# VentaConnected_ESP8266_V0_01_2017-11-26.net
KiCad netlist of a schematic drawn in EAGLE
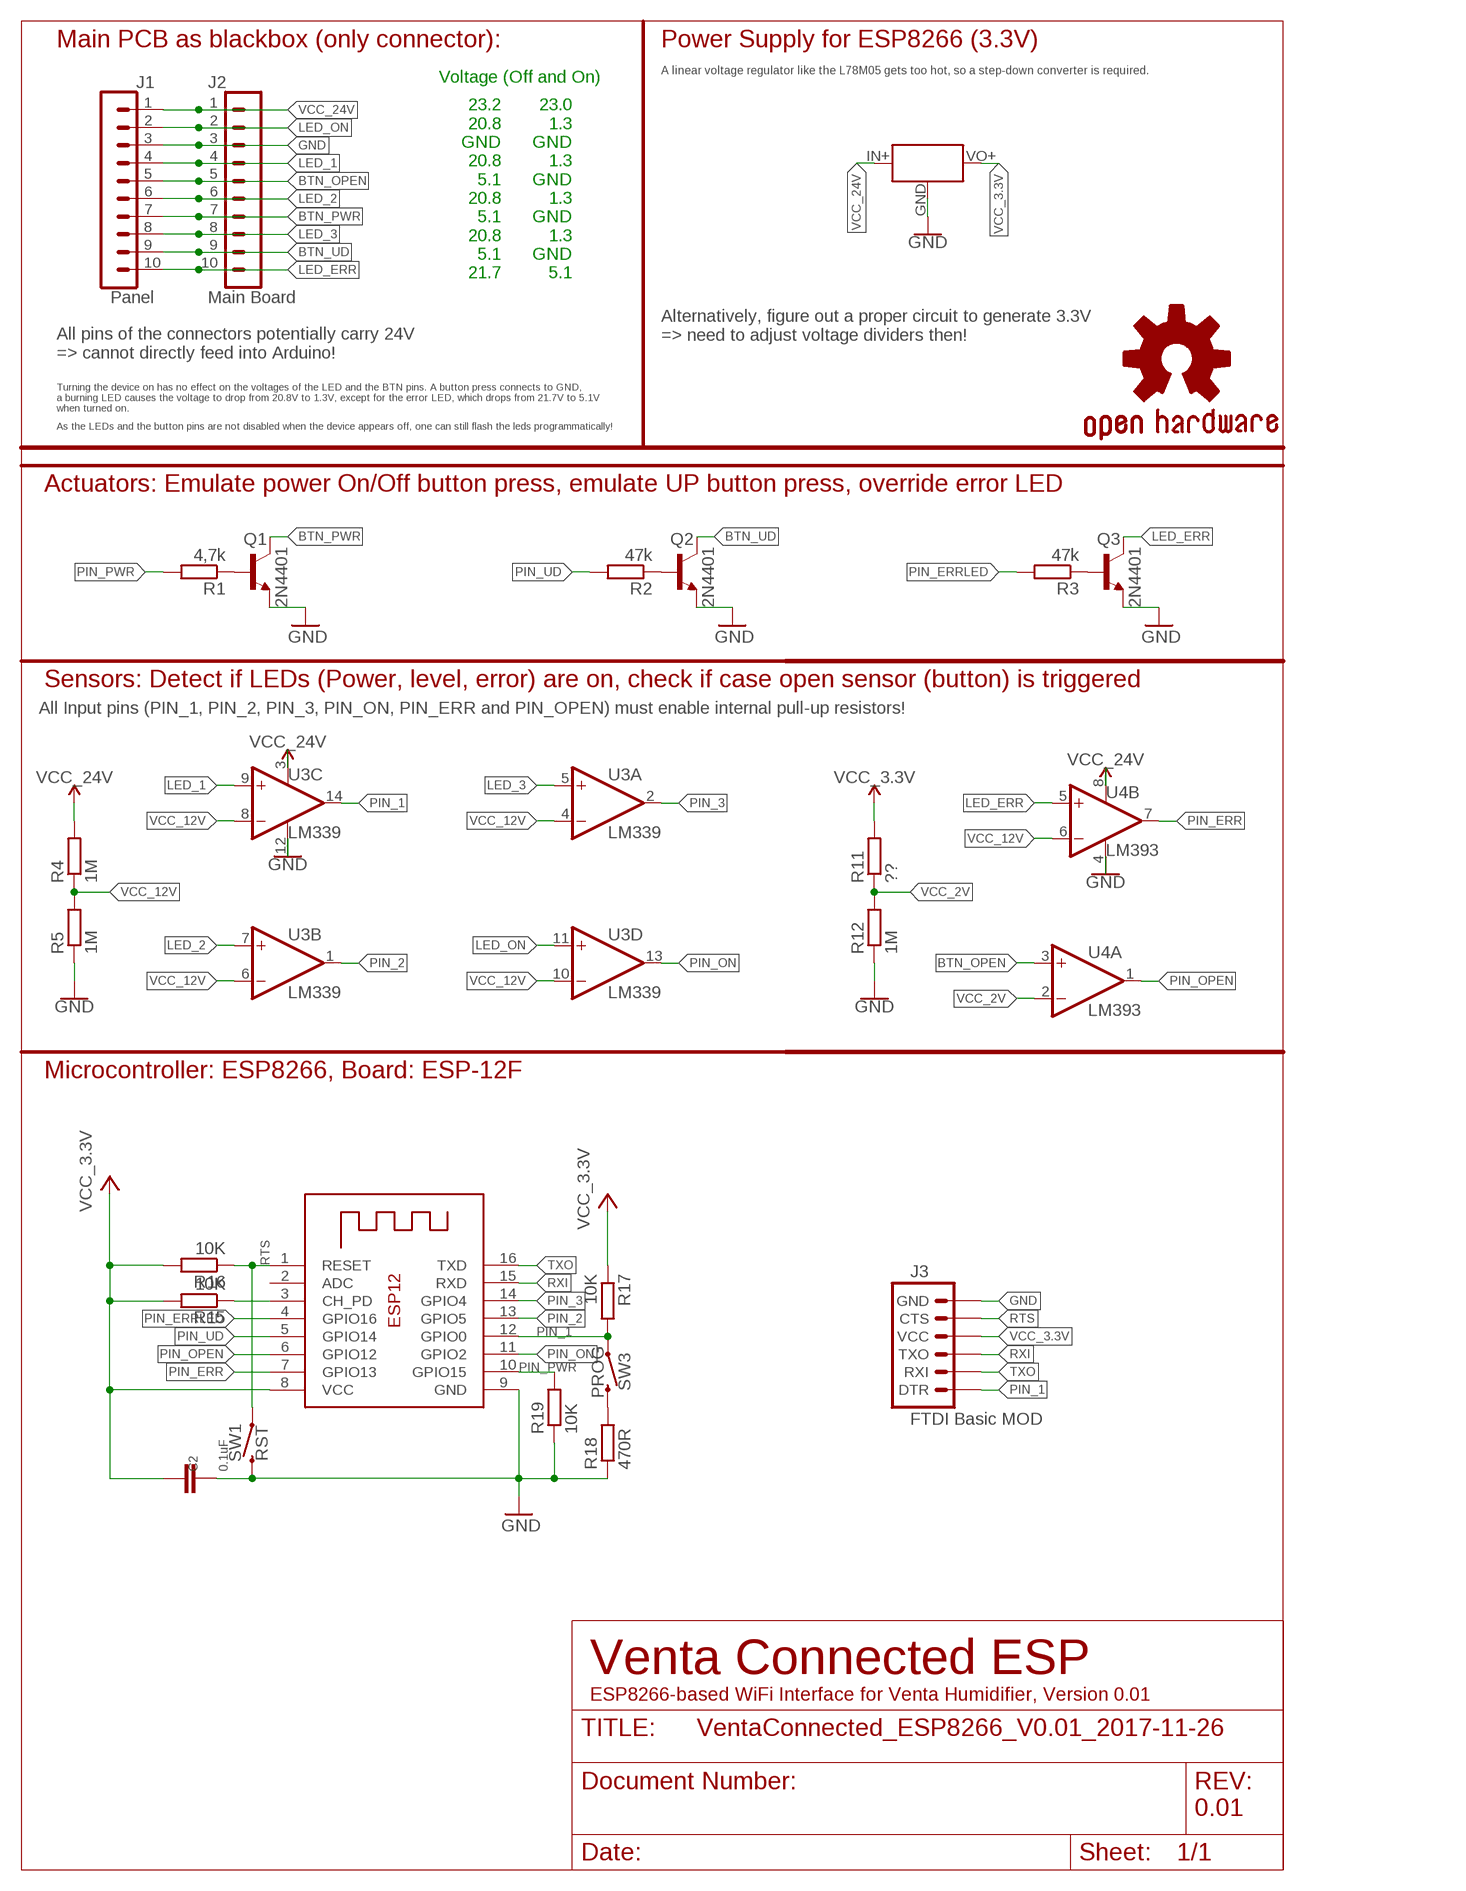
[diagram p0: schematic, sheet 1]

(export (version "E")
  (design (tool "Eeschema 10.0.6"))
  (components
    (comp (ref "C2")
      (value "0.1uF")
      (footprint "eagle-import:C0805")
      (libsource (lib "eagle-import") (part "C-EUC0805"))
    )
    (comp (ref "GOLD_ORB_SM1")
      (value "OSHWLOGO_GOLD_ORB_SM")
      (footprint "eagle-import:OSHW2")
      (libsource (lib "eagle-import") (part "OSHWLOGO_GOLD_ORB_SM"))
    )
    (comp (ref "J1")
      (value "Panel")
      (footprint "eagle-import:2X5-SHROUDED")
      (libsource (lib "eagle-import") (part "CONN_05X2SHD"))
    )
    (comp (ref "J2")
      (value "Main Board")
      (footprint "eagle-import:2X5")
      (libsource (lib "eagle-import") (part "CONN_05X2PTH"))
    )
    (comp (ref "J3")
      (value "FTDI Basic MOD")
      (footprint "eagle-import:1X06")
      (libsource (lib "eagle-import") (part "ARDUINO_SERIAL_PROGRAMPTH"))
    )
    (comp (ref "Q1")
      (value "2N4401")
      (footprint "eagle-import:SOT23-BEC")
      (libsource (lib "eagle-import") (part "-NPN-SOT23-BECMMBT4401LT1"))
    )
    (comp (ref "Q2")
      (value "2N4401")
      (footprint "eagle-import:SOT23-BEC")
      (libsource (lib "eagle-import") (part "-NPN-SOT23-BECMMBT4401LT1"))
    )
    (comp (ref "Q3")
      (value "2N4401")
      (footprint "eagle-import:SOT23-BEC")
      (libsource (lib "eagle-import") (part "-NPN-SOT23-BECMMBT4401LT1"))
    )
    (comp (ref "R1")
      (value "4,7k")
      (footprint "eagle-import:R0805")
      (libsource (lib "eagle-import") (part "resistor_348_R-EU_R0805"))
    )
    (comp (ref "R2")
      (value "47k")
      (footprint "eagle-import:R0805")
      (libsource (lib "eagle-import") (part "resistor_348_R-EU_R0805"))
    )
    (comp (ref "R3")
      (value "47k")
      (footprint "eagle-import:R0805")
      (libsource (lib "eagle-import") (part "resistor_348_R-EU_R0805"))
    )
    (comp (ref "R4")
      (value "1M")
      (footprint "eagle-import:R0805")
      (libsource (lib "eagle-import") (part "resistor_348_R-EU_R0805"))
    )
    (comp (ref "R5")
      (value "1M")
      (footprint "eagle-import:R0805")
      (libsource (lib "eagle-import") (part "resistor_348_R-EU_R0805"))
    )
    (comp (ref "R11")
      (value "??")
      (footprint "eagle-import:R0805")
      (libsource (lib "eagle-import") (part "resistor_348_R-EU_R0805"))
    )
    (comp (ref "R12")
      (value "1M")
      (footprint "eagle-import:R0805")
      (libsource (lib "eagle-import") (part "resistor_348_R-EU_R0805"))
    )
    (comp (ref "R15")
      (value "10K")
      (footprint "eagle-import:R0805")
      (libsource (lib "eagle-import") (part "R-EU_R0805"))
    )
    (comp (ref "R16")
      (value "10K")
      (footprint "eagle-import:R0805")
      (libsource (lib "eagle-import") (part "R-EU_R0805"))
    )
    (comp (ref "R17")
      (value "10K")
      (footprint "eagle-import:R0805")
      (libsource (lib "eagle-import") (part "R-EU_R0805"))
    )
    (comp (ref "R18")
      (value "470R")
      (footprint "eagle-import:R0805")
      (libsource (lib "eagle-import") (part "R-EU_R0805"))
    )
    (comp (ref "R19")
      (value "10K")
      (footprint "eagle-import:R0805")
      (libsource (lib "eagle-import") (part "R-EU_R0805"))
    )
    (comp (ref "SW1")
      (value "RST")
      (footprint "eagle-import:TACTILE_SWITCH_SMD_6.0X3.5MM")
      (libsource (lib "eagle-import") (part "MOMENTARY-SWITCH-SPST-SMD-6.0X3.5MM"))
    )
    (comp (ref "SW3")
      (value "PROG")
      (footprint "eagle-import:TACTILE_SWITCH_SMD_6.0X3.5MM")
      (libsource (lib "eagle-import") (part "MOMENTARY-SWITCH-SPST-SMD-6.0X3.5MM"))
    )
    (comp (ref "U2")
      (value "3.3V_BUCK_CONVERTER")
      (footprint "eagle-import:MINI_BUCK_CONVERTER_UPDOWN")
      (libsource (lib "eagle-import") (part "MINI_BUCK_CONVERTER_UPSIDEDOWN"))
    )
    (comp (ref "U3")
      (value "LM339")
      (footprint "eagle-import:SO14")
      (libsource (lib "eagle-import") (part "TLC339D"))
    )
    (comp (ref "U4")
      (value "LM393")
      (footprint "eagle-import:SO08")
      (libsource (lib "eagle-import") (part "LM393D"))
    )
    (comp (ref "X2")
      (value "ESP-12e")
      (footprint "eagle-import:ESP-12")
      (libsource (lib "eagle-import") (part "ESP-12"))
    )
  )
  (nets
    (net (code "1") (name "BTN_OPEN") (class "Default")
      (node (ref "J1") (pin "5") (pinfunction "5_5") (pintype "passive"))
      (node (ref "J2") (pin "5") (pinfunction "5_5") (pintype "passive"))
      (node (ref "U4") (pin "3") (pinfunction "+IN_3") (pintype "input"))
    )
    (net (code "2") (name "BTN_PWR") (class "Default")
      (node (ref "J1") (pin "7") (pinfunction "7_7") (pintype "passive"))
      (node (ref "J2") (pin "7") (pinfunction "7_7") (pintype "passive"))
      (node (ref "Q1") (pin "C") (pinfunction "C_C") (pintype "passive"))
    )
    (net (code "3") (name "BTN_UD") (class "Default")
      (node (ref "J1") (pin "9") (pinfunction "9_9") (pintype "passive"))
      (node (ref "J2") (pin "9") (pinfunction "9_9") (pintype "passive"))
      (node (ref "Q2") (pin "C") (pinfunction "C_C") (pintype "passive"))
    )
    (net (code "4") (name "GND") (class "Default")
      (node (ref "C2") (pin "1") (pinfunction "1_1") (pintype "passive"))
      (node (ref "J1") (pin "3") (pinfunction "3_3") (pintype "passive"))
      (node (ref "J2") (pin "3") (pinfunction "3_3") (pintype "passive"))
      (node (ref "J3") (pin "6") (pinfunction "GND_6") (pintype "passive"))
      (node (ref "Q1") (pin "E") (pinfunction "E_E") (pintype "passive"))
      (node (ref "Q2") (pin "E") (pinfunction "E_E") (pintype "passive"))
      (node (ref "Q3") (pin "E") (pinfunction "E_E") (pintype "passive"))
      (node (ref "R12") (pin "1") (pinfunction "1_1") (pintype "passive"))
      (node (ref "R18") (pin "1") (pinfunction "1_1") (pintype "passive"))
      (node (ref "R19") (pin "1") (pinfunction "1_1") (pintype "passive"))
      (node (ref "R5") (pin "1") (pinfunction "1_1") (pintype "passive"))
      (node (ref "SW1") (pin "2") (pinfunction "2_2") (pintype "passive"))
      (node (ref "U2") (pin "GND") (pinfunction "GND_GND") (pintype "bidirectional"))
      (node (ref "U3") (pin "12") (pinfunction "V-_12") (pintype "power_in"))
      (node (ref "U4") (pin "4") (pinfunction "V-_4") (pintype "power_in"))
      (node (ref "X2") (pin "9") (pinfunction "GND_9") (pintype "power_in"))
    )
    (net (code "5") (name "LED_1") (class "Default")
      (node (ref "J1") (pin "4") (pinfunction "4_4") (pintype "passive"))
      (node (ref "J2") (pin "4") (pinfunction "4_4") (pintype "passive"))
      (node (ref "U3") (pin "9") (pinfunction "+IN_9") (pintype "input"))
    )
    (net (code "6") (name "LED_2") (class "Default")
      (node (ref "J1") (pin "6") (pinfunction "6_6") (pintype "passive"))
      (node (ref "J2") (pin "6") (pinfunction "6_6") (pintype "passive"))
      (node (ref "U3") (pin "7") (pinfunction "+IN_7") (pintype "input"))
    )
    (net (code "7") (name "LED_3") (class "Default")
      (node (ref "J1") (pin "8") (pinfunction "8_8") (pintype "passive"))
      (node (ref "J2") (pin "8") (pinfunction "8_8") (pintype "passive"))
      (node (ref "U3") (pin "5") (pinfunction "+IN_5") (pintype "input"))
    )
    (net (code "8") (name "LED_ERR") (class "Default")
      (node (ref "J1") (pin "10") (pinfunction "10_10") (pintype "passive"))
      (node (ref "J2") (pin "10") (pinfunction "10_10") (pintype "passive"))
      (node (ref "Q3") (pin "C") (pinfunction "C_C") (pintype "passive"))
      (node (ref "U4") (pin "5") (pinfunction "+IN_5") (pintype "input"))
    )
    (net (code "9") (name "LED_ON") (class "Default")
      (node (ref "J1") (pin "2") (pinfunction "2_2") (pintype "passive"))
      (node (ref "J2") (pin "2") (pinfunction "2_2") (pintype "passive"))
      (node (ref "U3") (pin "11") (pinfunction "+IN_11") (pintype "input"))
    )
    (net (code "10") (name "Net-(Q1-PadB)") (class "Default")
      (node (ref "Q1") (pin "B") (pinfunction "B_B") (pintype "passive"))
      (node (ref "R1") (pin "1") (pinfunction "1_1") (pintype "passive"))
    )
    (net (code "11") (name "Net-(Q2-PadB)") (class "Default")
      (node (ref "Q2") (pin "B") (pinfunction "B_B") (pintype "passive"))
      (node (ref "R2") (pin "1") (pinfunction "1_1") (pintype "passive"))
    )
    (net (code "12") (name "Net-(Q3-PadB)") (class "Default")
      (node (ref "Q3") (pin "B") (pinfunction "B_B") (pintype "passive"))
      (node (ref "R3") (pin "1") (pinfunction "1_1") (pintype "passive"))
    )
    (net (code "13") (name "Net-(R18-Pad2)") (class "Default")
      (node (ref "R18") (pin "2") (pinfunction "2_2") (pintype "passive"))
      (node (ref "SW3") (pin "2") (pinfunction "2_2") (pintype "passive"))
    )
    (net (code "14") (name "Net-(X2-CH_PD)") (class "Default")
      (node (ref "R15") (pin "1") (pinfunction "1_1") (pintype "passive"))
      (node (ref "X2") (pin "3") (pinfunction "CH_PD_3") (pintype "input"))
    )
    (net (code "15") (name "PIN_1") (class "Default")
      (node (ref "J3") (pin "1") (pinfunction "DTR_1") (pintype "passive"))
      (node (ref "R17") (pin "2") (pinfunction "2_2") (pintype "passive"))
      (node (ref "SW3") (pin "1") (pinfunction "1_1") (pintype "passive"))
      (node (ref "U3") (pin "14") (pinfunction "OUT_14") (pintype "output"))
      (node (ref "X2") (pin "12") (pinfunction "GPIO0_12") (pintype "bidirectional"))
    )
    (net (code "16") (name "PIN_2") (class "Default")
      (node (ref "U3") (pin "1") (pinfunction "OUT_1") (pintype "output"))
      (node (ref "X2") (pin "13") (pinfunction "GPIO5_13") (pintype "bidirectional"))
    )
    (net (code "17") (name "PIN_3") (class "Default")
      (node (ref "U3") (pin "2") (pinfunction "OUT_2") (pintype "output"))
      (node (ref "X2") (pin "14") (pinfunction "GPIO4_14") (pintype "bidirectional"))
    )
    (net (code "18") (name "PIN_ERR") (class "Default")
      (node (ref "U4") (pin "7") (pinfunction "OUT_7") (pintype "output"))
      (node (ref "X2") (pin "7") (pinfunction "GPIO13_7") (pintype "bidirectional"))
    )
    (net (code "19") (name "PIN_ERRLED") (class "Default")
      (node (ref "R3") (pin "2") (pinfunction "2_2") (pintype "passive"))
      (node (ref "X2") (pin "4") (pinfunction "GPIO16_4") (pintype "bidirectional"))
    )
    (net (code "20") (name "PIN_ON") (class "Default")
      (node (ref "U3") (pin "13") (pinfunction "OUT_13") (pintype "output"))
      (node (ref "X2") (pin "11") (pinfunction "GPIO2_11") (pintype "bidirectional"))
    )
    (net (code "21") (name "PIN_OPEN") (class "Default")
      (node (ref "U4") (pin "1") (pinfunction "OUT_1") (pintype "output"))
      (node (ref "X2") (pin "6") (pinfunction "GPIO12_6") (pintype "bidirectional"))
    )
    (net (code "22") (name "PIN_PWR") (class "Default")
      (node (ref "R1") (pin "2") (pinfunction "2_2") (pintype "passive"))
      (node (ref "R19") (pin "2") (pinfunction "2_2") (pintype "passive"))
      (node (ref "X2") (pin "10") (pinfunction "GPIO15_10") (pintype "bidirectional"))
    )
    (net (code "23") (name "PIN_UD") (class "Default")
      (node (ref "R2") (pin "2") (pinfunction "2_2") (pintype "passive"))
      (node (ref "X2") (pin "5") (pinfunction "GPIO14_5") (pintype "bidirectional"))
    )
    (net (code "24") (name "RTS") (class "Default")
      (node (ref "J3") (pin "5") (pinfunction "CTS_5") (pintype "passive"))
      (node (ref "R16") (pin "1") (pinfunction "1_1") (pintype "passive"))
      (node (ref "SW1") (pin "1") (pinfunction "1_1") (pintype "passive"))
      (node (ref "X2") (pin "1") (pinfunction "RESET_1") (pintype "input"))
    )
    (net (code "25") (name "RXI") (class "Default")
      (node (ref "J3") (pin "3") (pinfunction "TXO_3") (pintype "passive"))
      (node (ref "X2") (pin "15") (pinfunction "RXD_15") (pintype "input"))
    )
    (net (code "26") (name "TXO") (class "Default")
      (node (ref "J3") (pin "2") (pinfunction "RXI_2") (pintype "passive"))
      (node (ref "X2") (pin "16") (pinfunction "TXD_16") (pintype "output"))
    )
    (net (code "27") (name "VCC_2V") (class "Default")
      (node (ref "R11") (pin "1") (pinfunction "1_1") (pintype "passive"))
      (node (ref "R12") (pin "2") (pinfunction "2_2") (pintype "passive"))
      (node (ref "U4") (pin "2") (pinfunction "-IN_2") (pintype "input"))
    )
    (net (code "28") (name "VCC_3.3V") (class "Default")
      (node (ref "C2") (pin "2") (pinfunction "2_2") (pintype "passive"))
      (node (ref "J3") (pin "4") (pinfunction "VCC_4") (pintype "passive"))
      (node (ref "R11") (pin "2") (pinfunction "2_2") (pintype "passive"))
      (node (ref "R15") (pin "2") (pinfunction "2_2") (pintype "passive"))
      (node (ref "R16") (pin "2") (pinfunction "2_2") (pintype "passive"))
      (node (ref "R17") (pin "1") (pinfunction "1_1") (pintype "passive"))
      (node (ref "U2") (pin "VO+") (pinfunction "VOUT_VO+") (pintype "power_in"))
      (node (ref "X2") (pin "8") (pinfunction "VCC_8") (pintype "power_in"))
    )
    (net (code "29") (name "VCC_12V") (class "Default")
      (node (ref "R4") (pin "1") (pinfunction "1_1") (pintype "passive"))
      (node (ref "R5") (pin "2") (pinfunction "2_2") (pintype "passive"))
      (node (ref "U3") (pin "10") (pinfunction "-IN_10") (pintype "input"))
      (node (ref "U3") (pin "4") (pinfunction "-IN_4") (pintype "input"))
      (node (ref "U3") (pin "6") (pinfunction "-IN_6") (pintype "input"))
      (node (ref "U3") (pin "8") (pinfunction "-IN_8") (pintype "input"))
      (node (ref "U4") (pin "6") (pinfunction "-IN_6") (pintype "input"))
    )
    (net (code "30") (name "VCC_24V") (class "Default")
      (node (ref "J1") (pin "1") (pinfunction "1_1") (pintype "passive"))
      (node (ref "J2") (pin "1") (pinfunction "1_1") (pintype "passive"))
      (node (ref "R4") (pin "2") (pinfunction "2_2") (pintype "passive"))
      (node (ref "U2") (pin "IN+") (pinfunction "VIN_IN+") (pintype "input"))
      (node (ref "U3") (pin "3") (pinfunction "V+_3") (pintype "power_in"))
      (node (ref "U4") (pin "8") (pinfunction "V+_8") (pintype "power_in"))
    )
    (net (code "31") (name "unconnected-(X2-ADC-Pad2)") (class "Default")
      (node (ref "X2") (pin "2") (pinfunction "ADC_2") (pintype "passive"))
    )
  )
)
